# Podk_adka_pod_kubek_2_Bartosz_K_pa.net
KiCad netlist of a schematic drawn in EAGLE
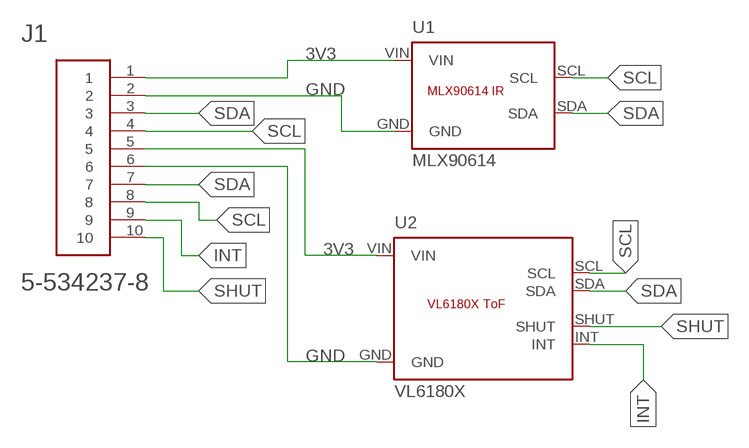
[diagram p0: schematic, sheet 1]

(export (version "E")
  (design (tool "Eeschema 10.0.6"))
  (components
    (comp (ref "J1")
      (value "5-534237-8")
      (footprint "eagle-import:5-534237-8")
      (fields
        (field (name "DIGIKEY_PART_NUMBER") "A32910-ND")
        (field (name "MANUFACTURER") "TE Connectivity AMP Connectors")
        (field (name "CREATED_BY") " PCBLayout.com")
      )
      (libsource (lib "eagle-import") (part "5-534237-8"))
    )
    (comp (ref "U1")
      (value "MLX90614")
      (footprint "eagle-import:MLX90614_MODULE")
      (libsource (lib "eagle-import") (part "MLX90614"))
    )
    (comp (ref "U2")
      (value "VL6180X")
      (footprint "eagle-import:VL6180X_MODULE")
      (libsource (lib "eagle-import") (part "VL6180X"))
    )
  )
  (nets
    (net (code "1") (name "/3V3") (class "Default")
      (node (ref "J1") (pin "1") (pinfunction "1_1") (pintype "passive"))
      (node (ref "J1") (pin "5") (pinfunction "5_5") (pintype "passive"))
      (node (ref "U1") (pin "VIN") (pinfunction "VIN_VIN") (pintype "power_in"))
      (node (ref "U2") (pin "VIN") (pinfunction "VIN_VIN") (pintype "power_in"))
    )
    (net (code "2") (name "/GND") (class "Default")
      (node (ref "J1") (pin "2") (pinfunction "2_2") (pintype "passive"))
      (node (ref "J1") (pin "6") (pinfunction "6_6") (pintype "passive"))
      (node (ref "U1") (pin "GND") (pinfunction "GND_GND") (pintype "power_in"))
      (node (ref "U2") (pin "GND") (pinfunction "GND_GND") (pintype "power_in"))
    )
    (net (code "3") (name "INT") (class "Default")
      (node (ref "J1") (pin "9") (pinfunction "9_9") (pintype "passive"))
      (node (ref "U2") (pin "INT") (pinfunction "INT_INT") (pintype "bidirectional"))
    )
    (net (code "4") (name "SCL") (class "Default")
      (node (ref "J1") (pin "4") (pinfunction "4_4") (pintype "passive"))
      (node (ref "J1") (pin "8") (pinfunction "8_8") (pintype "passive"))
      (node (ref "U1") (pin "SCL") (pinfunction "SCL_SCL") (pintype "bidirectional"))
      (node (ref "U2") (pin "SCL") (pinfunction "SCL_SCL") (pintype "bidirectional"))
    )
    (net (code "5") (name "SDA") (class "Default")
      (node (ref "J1") (pin "3") (pinfunction "3_3") (pintype "passive"))
      (node (ref "J1") (pin "7") (pinfunction "7_7") (pintype "passive"))
      (node (ref "U1") (pin "SDA") (pinfunction "SDA_SDA") (pintype "bidirectional"))
      (node (ref "U2") (pin "SDA") (pinfunction "SDA_SDA") (pintype "bidirectional"))
    )
    (net (code "6") (name "SHUT") (class "Default")
      (node (ref "J1") (pin "10") (pinfunction "10_10") (pintype "passive"))
      (node (ref "U2") (pin "SHUT") (pinfunction "SHUT_SHUT") (pintype "bidirectional"))
    )
  )
)
